# Rocket32_TRASIO_fixed.net
KiCad netlist of a schematic drawn in EAGLE
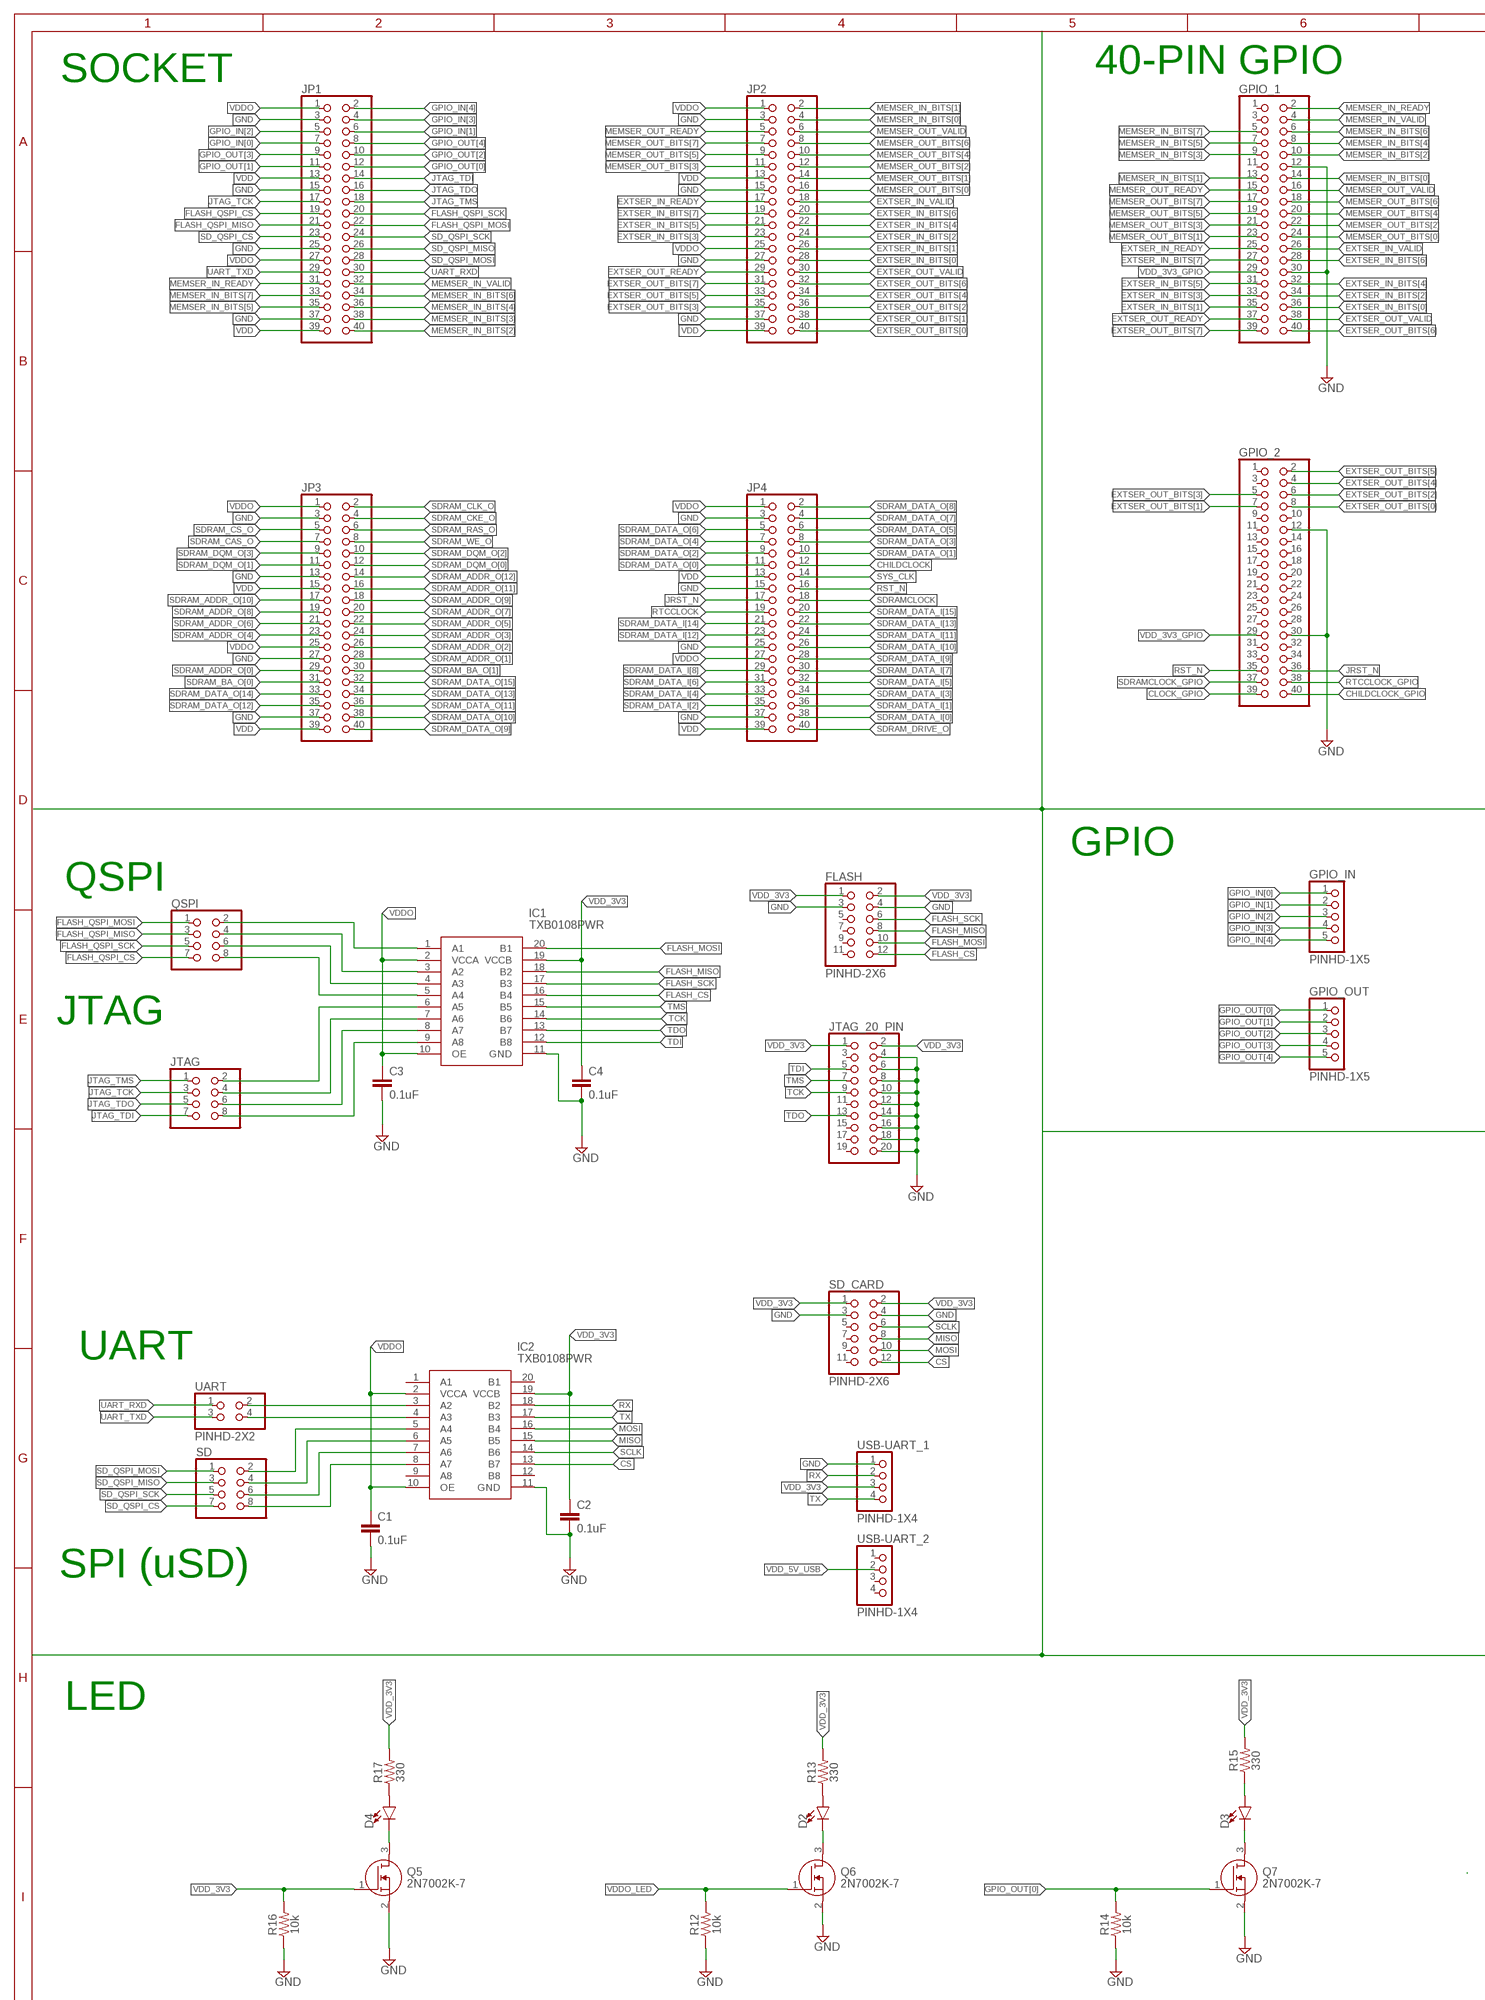
[diagram p0: schematic, sheet 1, part 1 of 2]
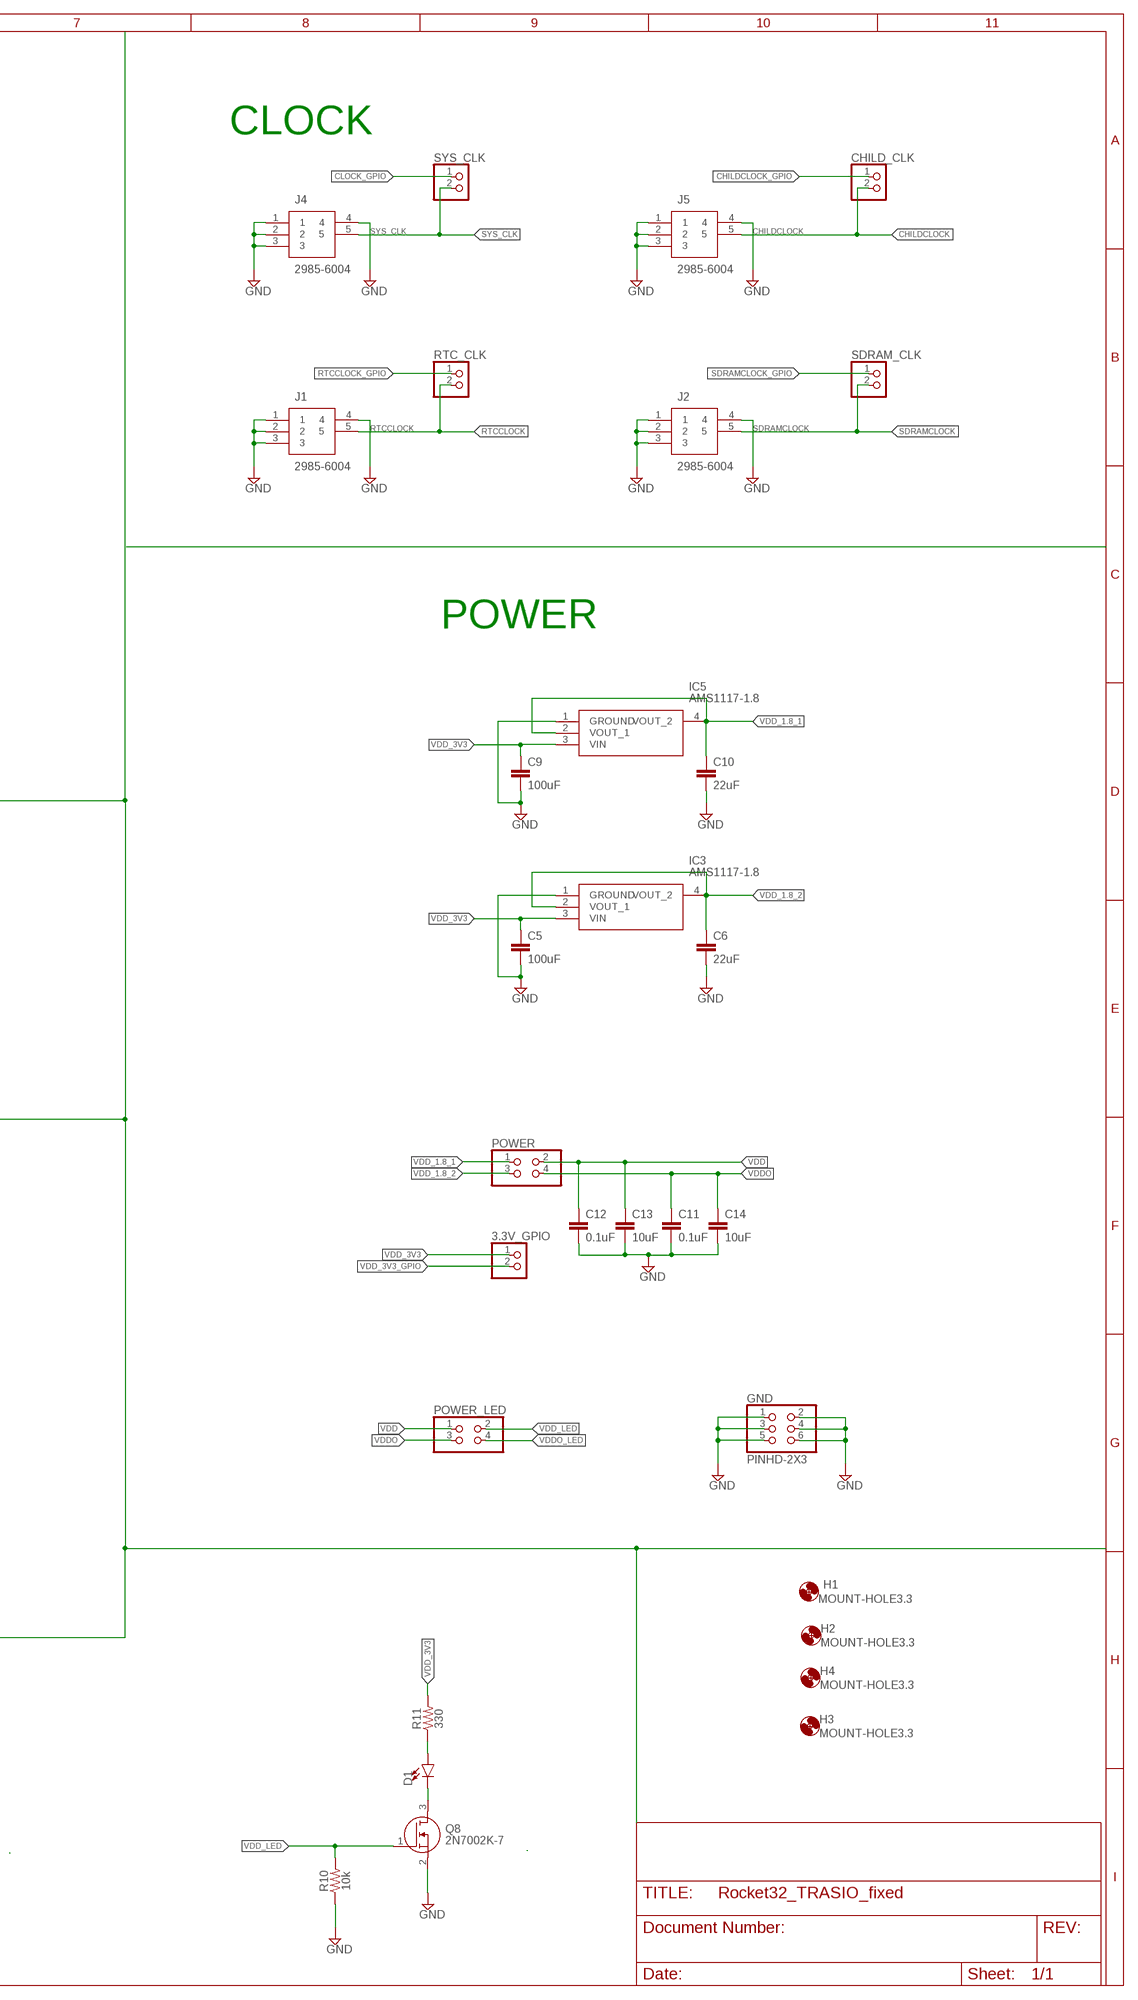
[diagram p1: schematic, sheet 1, part 2 of 2]

(export (version "E")
  (design (tool "Eeschema 10.0.6"))
  (components
    (comp (ref "3.3V_GPIO")
      (value "PINHD-1X2")
      (footprint "eagle-import:1X02")
      (libsource (lib "eagle-import") (part "PINHD-1X2"))
    )
    (comp (ref "C1")
      (value "0.1uF")
      (footprint "eagle-import:1206")
      (libsource (lib "eagle-import") (part "1.0UF-1206-50V-10%"))
    )
    (comp (ref "C2")
      (value "0.1uF")
      (footprint "eagle-import:1206")
      (libsource (lib "eagle-import") (part "1.0UF-1206-50V-10%"))
    )
    (comp (ref "C3")
      (value "0.1uF")
      (footprint "eagle-import:1206")
      (libsource (lib "eagle-import") (part "1.0UF-1206-50V-10%"))
    )
    (comp (ref "C4")
      (value "0.1uF")
      (footprint "eagle-import:1206")
      (libsource (lib "eagle-import") (part "1.0UF-1206-50V-10%"))
    )
    (comp (ref "C5")
      (value "100uF")
      (footprint "eagle-import:1206")
      (libsource (lib "eagle-import") (part "1.0UF-1206-50V-10%"))
    )
    (comp (ref "C6")
      (value "22uF")
      (footprint "eagle-import:1206")
      (libsource (lib "eagle-import") (part "1.0UF-1206-50V-10%"))
    )
    (comp (ref "C9")
      (value "100uF")
      (footprint "eagle-import:1206")
      (libsource (lib "eagle-import") (part "1.0UF-1206-50V-10%"))
    )
    (comp (ref "C10")
      (value "22uF")
      (footprint "eagle-import:1206")
      (libsource (lib "eagle-import") (part "1.0UF-1206-50V-10%"))
    )
    (comp (ref "C11")
      (value "0.1uF")
      (footprint "eagle-import:1206")
      (libsource (lib "eagle-import") (part "1.0UF-1206-50V-10%"))
    )
    (comp (ref "C12")
      (value "0.1uF")
      (footprint "eagle-import:1206")
      (libsource (lib "eagle-import") (part "1.0UF-1206-50V-10%"))
    )
    (comp (ref "C13")
      (value "10uF")
      (footprint "eagle-import:1206")
      (libsource (lib "eagle-import") (part "1.0UF-1206-50V-10%"))
    )
    (comp (ref "C14")
      (value "10uF")
      (footprint "eagle-import:1206")
      (libsource (lib "eagle-import") (part "1.0UF-1206-50V-10%"))
    )
    (comp (ref "CHILD_CLK")
      (value "PINHD-1X2")
      (footprint "eagle-import:1X02")
      (libsource (lib "eagle-import") (part "PINHD-1X2"))
    )
    (comp (ref "D1")
      (value "LED1206")
      (footprint "eagle-import:LED-1206")
      (libsource (lib "eagle-import") (part "LED1206"))
    )
    (comp (ref "D2")
      (value "LED1206")
      (footprint "eagle-import:LED-1206")
      (libsource (lib "eagle-import") (part "LED1206"))
    )
    (comp (ref "D3")
      (value "LED1206")
      (footprint "eagle-import:LED-1206")
      (libsource (lib "eagle-import") (part "LED1206"))
    )
    (comp (ref "D4")
      (value "LED1206")
      (footprint "eagle-import:LED-1206")
      (libsource (lib "eagle-import") (part "LED1206"))
    )
    (comp (ref "FLASH")
      (value "PINHD-2X6")
      (footprint "eagle-import:2X06")
      (libsource (lib "eagle-import") (part "PINHD-2X6"))
    )
    (comp (ref "GND")
      (value "PINHD-2X3")
      (footprint "eagle-import:2X03")
      (libsource (lib "eagle-import") (part "PINHD-2X3"))
    )
    (comp (ref "GPIO_1")
      (value "PINHD-2X20")
      (footprint "eagle-import:2X20")
      (libsource (lib "eagle-import") (part "PINHD-2X20"))
    )
    (comp (ref "GPIO_2")
      (value "PINHD-2X20")
      (footprint "eagle-import:2X20")
      (libsource (lib "eagle-import") (part "PINHD-2X20"))
    )
    (comp (ref "GPIO_IN")
      (value "PINHD-1X5")
      (footprint "eagle-import:1X05")
      (libsource (lib "eagle-import") (part "PINHD-1X5"))
    )
    (comp (ref "GPIO_OUT")
      (value "PINHD-1X5")
      (footprint "eagle-import:1X05")
      (libsource (lib "eagle-import") (part "PINHD-1X5"))
    )
    (comp (ref "H1")
      (value "MOUNT-HOLE3.3")
      (footprint "eagle-import:3,3")
      (libsource (lib "eagle-import") (part "MOUNT-HOLE3.3"))
    )
    (comp (ref "H2")
      (value "MOUNT-HOLE3.3")
      (footprint "eagle-import:3,3")
      (libsource (lib "eagle-import") (part "MOUNT-HOLE3.3"))
    )
    (comp (ref "H3")
      (value "MOUNT-HOLE3.3")
      (footprint "eagle-import:3,3")
      (libsource (lib "eagle-import") (part "MOUNT-HOLE3.3"))
    )
    (comp (ref "H4")
      (value "MOUNT-HOLE3.3")
      (footprint "eagle-import:3,3")
      (libsource (lib "eagle-import") (part "MOUNT-HOLE3.3"))
    )
    (comp (ref "IC1")
      (value "TXB0108PWR")
      (footprint "eagle-import:SOP65P640X120-20N")
      (fields (field (name "MOUSER_PART_NUMBER") "595-TXB0108PWR"))
      (libsource (lib "eagle-import") (part "TXB0108PWR"))
    )
    (comp (ref "IC2")
      (value "TXB0108PWR")
      (footprint "eagle-import:SOP65P640X120-20N")
      (fields (field (name "MOUSER_PART_NUMBER") "595-TXB0108PWR"))
      (libsource (lib "eagle-import") (part "TXB0108PWR"))
    )
    (comp (ref "IC3")
      (value "AMS1117-1.8")
      (footprint "eagle-import:SOT229P700X180-4N")
      (fields (field (name "MANUFACTURER_PART_NUMBER") "AMS1117"))
      (libsource (lib "eagle-import") (part "AMS1117"))
    )
    (comp (ref "IC5")
      (value "AMS1117-1.8")
      (footprint "eagle-import:SOT229P700X180-4N")
      (fields (field (name "MANUFACTURER_PART_NUMBER") "AMS1117"))
      (libsource (lib "eagle-import") (part "AMS1117"))
    )
    (comp (ref "J1")
      (value "2985-6004")
      (footprint "eagle-import:29856004")
      (fields (field (name "MOUSER_PART_NUMBER") "523-2985-6004"))
      (libsource (lib "eagle-import") (part "2985-6004"))
    )
    (comp (ref "J2")
      (value "2985-6004")
      (footprint "eagle-import:29856004")
      (fields (field (name "MOUSER_PART_NUMBER") "523-2985-6004"))
      (libsource (lib "eagle-import") (part "2985-6004"))
    )
    (comp (ref "J4")
      (value "2985-6004")
      (footprint "eagle-import:29856004")
      (fields (field (name "MOUSER_PART_NUMBER") "523-2985-6004"))
      (libsource (lib "eagle-import") (part "2985-6004"))
    )
    (comp (ref "J5")
      (value "2985-6004")
      (footprint "eagle-import:29856004")
      (fields (field (name "MOUSER_PART_NUMBER") "523-2985-6004"))
      (libsource (lib "eagle-import") (part "2985-6004"))
    )
    (comp (ref "JP1")
      (value "PINHD-2X20")
      (footprint "eagle-import:2X20")
      (libsource (lib "eagle-import") (part "PINHD-2X20"))
    )
    (comp (ref "JP2")
      (value "PINHD-2X20")
      (footprint "eagle-import:2X20")
      (libsource (lib "eagle-import") (part "PINHD-2X20"))
    )
    (comp (ref "JP3")
      (value "PINHD-2X20")
      (footprint "eagle-import:2X20")
      (libsource (lib "eagle-import") (part "PINHD-2X20"))
    )
    (comp (ref "JP4")
      (value "PINHD-2X20")
      (footprint "eagle-import:2X20")
      (libsource (lib "eagle-import") (part "PINHD-2X20"))
    )
    (comp (ref "JTAG")
      (value "PINHD-2X4")
      (footprint "eagle-import:2X04")
      (libsource (lib "eagle-import") (part "PINHD-2X4"))
    )
    (comp (ref "JTAG_20_PIN")
      (value "PINHD-2X10")
      (footprint "eagle-import:2X10")
      (libsource (lib "eagle-import") (part "PINHD-2X10"))
    )
    (comp (ref "POWER")
      (value "PINHD-2X2")
      (footprint "eagle-import:2X02")
      (libsource (lib "eagle-import") (part "pinhead_325_PINHD-2X2"))
    )
    (comp (ref "POWER_LED")
      (value "PINHD-2X2")
      (footprint "eagle-import:2X02")
      (libsource (lib "eagle-import") (part "pinhead_325_PINHD-2X2"))
    )
    (comp (ref "Q5")
      (value "2N7002K-7")
      (footprint "eagle-import:SOT96P240X100-3N")
      (fields (field (name "MOUSER_PART_NUMBER") "621-2N7002K-7"))
      (libsource (lib "eagle-import") (part "2N7002K-7"))
    )
    (comp (ref "Q6")
      (value "2N7002K-7")
      (footprint "eagle-import:SOT96P240X100-3N")
      (fields (field (name "MOUSER_PART_NUMBER") "621-2N7002K-7"))
      (libsource (lib "eagle-import") (part "2N7002K-7"))
    )
    (comp (ref "Q7")
      (value "2N7002K-7")
      (footprint "eagle-import:SOT96P240X100-3N")
      (fields (field (name "MOUSER_PART_NUMBER") "621-2N7002K-7"))
      (libsource (lib "eagle-import") (part "2N7002K-7"))
    )
    (comp (ref "Q8")
      (value "2N7002K-7")
      (footprint "eagle-import:SOT96P240X100-3N")
      (fields (field (name "MOUSER_PART_NUMBER") "621-2N7002K-7"))
      (libsource (lib "eagle-import") (part "2N7002K-7"))
    )
    (comp (ref "QSPI")
      (value "PINHD-2X4")
      (footprint "eagle-import:2X04")
      (libsource (lib "eagle-import") (part "PINHD-2X4"))
    )
    (comp (ref "R10")
      (value "10k")
      (footprint "eagle-import:1206")
      (libsource (lib "eagle-import") (part "RESISTOR1206"))
    )
    (comp (ref "R11")
      (value "330")
      (footprint "eagle-import:1206")
      (libsource (lib "eagle-import") (part "RESISTOR1206"))
    )
    (comp (ref "R12")
      (value "10k")
      (footprint "eagle-import:1206")
      (libsource (lib "eagle-import") (part "RESISTOR1206"))
    )
    (comp (ref "R13")
      (value "330")
      (footprint "eagle-import:1206")
      (libsource (lib "eagle-import") (part "RESISTOR1206"))
    )
    (comp (ref "R14")
      (value "10k")
      (footprint "eagle-import:1206")
      (libsource (lib "eagle-import") (part "RESISTOR1206"))
    )
    (comp (ref "R15")
      (value "330")
      (footprint "eagle-import:1206")
      (libsource (lib "eagle-import") (part "RESISTOR1206"))
    )
    (comp (ref "R16")
      (value "10k")
      (footprint "eagle-import:1206")
      (libsource (lib "eagle-import") (part "RESISTOR1206"))
    )
    (comp (ref "R17")
      (value "330")
      (footprint "eagle-import:1206")
      (libsource (lib "eagle-import") (part "RESISTOR1206"))
    )
    (comp (ref "RTC_CLK")
      (value "PINHD-1X2")
      (footprint "eagle-import:1X02")
      (libsource (lib "eagle-import") (part "PINHD-1X2"))
    )
    (comp (ref "SD")
      (value "PINHD-2X4")
      (footprint "eagle-import:2X04")
      (libsource (lib "eagle-import") (part "PINHD-2X4"))
    )
    (comp (ref "SDRAM_CLK")
      (value "PINHD-1X2")
      (footprint "eagle-import:1X02")
      (libsource (lib "eagle-import") (part "PINHD-1X2"))
    )
    (comp (ref "SD_CARD")
      (value "PINHD-2X6")
      (footprint "eagle-import:2X06")
      (libsource (lib "eagle-import") (part "PINHD-2X6"))
    )
    (comp (ref "SYS_CLK")
      (value "PINHD-1X2")
      (footprint "eagle-import:1X02")
      (libsource (lib "eagle-import") (part "PINHD-1X2"))
    )
    (comp (ref "UART")
      (value "PINHD-2X2")
      (footprint "eagle-import:2X02")
      (libsource (lib "eagle-import") (part "PINHD-2X2"))
    )
    (comp (ref "USB-UART_1")
      (value "PINHD-1X4")
      (footprint "eagle-import:1X04")
      (libsource (lib "eagle-import") (part "PINHD-1X4"))
    )
    (comp (ref "USB-UART_2")
      (value "PINHD-1X4")
      (footprint "eagle-import:1X04")
      (libsource (lib "eagle-import") (part "PINHD-1X4"))
    )
  )
  (nets
    (net (code "1") (name "CHILDCLOCK") (class "Default")
      (node (ref "CHILD_CLK") (pin "2") (pinfunction "2_2") (pintype "passive"))
      (node (ref "J5") (pin "5") (pinfunction "5_5") (pintype "bidirectional"))
      (node (ref "JP4") (pin "12") (pinfunction "12_12") (pintype "passive"))
    )
    (net (code "2") (name "CHILDCLOCK_GPIO") (class "Default")
      (node (ref "CHILD_CLK") (pin "1") (pinfunction "1_1") (pintype "passive"))
      (node (ref "GPIO_2") (pin "40") (pinfunction "40_40") (pintype "passive"))
    )
    (net (code "3") (name "CLOCK_GPIO") (class "Default")
      (node (ref "GPIO_2") (pin "39") (pinfunction "39_39") (pintype "passive"))
      (node (ref "SYS_CLK") (pin "1") (pinfunction "1_1") (pintype "passive"))
    )
    (net (code "4") (name "CS") (class "Default")
      (node (ref "IC2") (pin "13") (pinfunction "B7_13") (pintype "bidirectional"))
      (node (ref "SD_CARD") (pin "12") (pinfunction "12_12") (pintype "passive"))
    )
    (net (code "5") (name "EXTSER_IN_BITS[0]") (class "Default")
      (node (ref "GPIO_1") (pin "36") (pinfunction "36_36") (pintype "passive"))
      (node (ref "JP2") (pin "28") (pinfunction "28_28") (pintype "passive"))
    )
    (net (code "6") (name "EXTSER_IN_BITS[1]") (class "Default")
      (node (ref "GPIO_1") (pin "35") (pinfunction "35_35") (pintype "passive"))
      (node (ref "JP2") (pin "26") (pinfunction "26_26") (pintype "passive"))
    )
    (net (code "7") (name "EXTSER_IN_BITS[2]") (class "Default")
      (node (ref "GPIO_1") (pin "34") (pinfunction "34_34") (pintype "passive"))
      (node (ref "JP2") (pin "24") (pinfunction "24_24") (pintype "passive"))
    )
    (net (code "8") (name "EXTSER_IN_BITS[3]") (class "Default")
      (node (ref "GPIO_1") (pin "33") (pinfunction "33_33") (pintype "passive"))
      (node (ref "JP2") (pin "23") (pinfunction "23_23") (pintype "passive"))
    )
    (net (code "9") (name "EXTSER_IN_BITS[4]") (class "Default")
      (node (ref "GPIO_1") (pin "32") (pinfunction "32_32") (pintype "passive"))
      (node (ref "JP2") (pin "22") (pinfunction "22_22") (pintype "passive"))
    )
    (net (code "10") (name "EXTSER_IN_BITS[5]") (class "Default")
      (node (ref "GPIO_1") (pin "31") (pinfunction "31_31") (pintype "passive"))
      (node (ref "JP2") (pin "21") (pinfunction "21_21") (pintype "passive"))
    )
    (net (code "11") (name "EXTSER_IN_BITS[6]") (class "Default")
      (node (ref "GPIO_1") (pin "28") (pinfunction "28_28") (pintype "passive"))
      (node (ref "JP2") (pin "20") (pinfunction "20_20") (pintype "passive"))
    )
    (net (code "12") (name "EXTSER_IN_BITS[7]") (class "Default")
      (node (ref "GPIO_1") (pin "27") (pinfunction "27_27") (pintype "passive"))
      (node (ref "JP2") (pin "19") (pinfunction "19_19") (pintype "passive"))
    )
    (net (code "13") (name "EXTSER_IN_READY") (class "Default")
      (node (ref "GPIO_1") (pin "25") (pinfunction "25_25") (pintype "passive"))
      (node (ref "JP2") (pin "17") (pinfunction "17_17") (pintype "passive"))
    )
    (net (code "14") (name "EXTSER_IN_VALID") (class "Default")
      (node (ref "GPIO_1") (pin "26") (pinfunction "26_26") (pintype "passive"))
      (node (ref "JP2") (pin "18") (pinfunction "18_18") (pintype "passive"))
    )
    (net (code "15") (name "EXTSER_OUT_BITS[0]") (class "Default")
      (node (ref "GPIO_2") (pin "8") (pinfunction "8_8") (pintype "passive"))
      (node (ref "JP2") (pin "40") (pinfunction "40_40") (pintype "passive"))
    )
    (net (code "16") (name "EXTSER_OUT_BITS[1]") (class "Default")
      (node (ref "GPIO_2") (pin "7") (pinfunction "7_7") (pintype "passive"))
      (node (ref "JP2") (pin "38") (pinfunction "38_38") (pintype "passive"))
    )
    (net (code "17") (name "EXTSER_OUT_BITS[2]") (class "Default")
      (node (ref "GPIO_2") (pin "6") (pinfunction "6_6") (pintype "passive"))
      (node (ref "JP2") (pin "36") (pinfunction "36_36") (pintype "passive"))
    )
    (net (code "18") (name "EXTSER_OUT_BITS[3]") (class "Default")
      (node (ref "GPIO_2") (pin "5") (pinfunction "5_5") (pintype "passive"))
      (node (ref "JP2") (pin "35") (pinfunction "35_35") (pintype "passive"))
    )
    (net (code "19") (name "EXTSER_OUT_BITS[4]") (class "Default")
      (node (ref "GPIO_2") (pin "4") (pinfunction "4_4") (pintype "passive"))
      (node (ref "JP2") (pin "34") (pinfunction "34_34") (pintype "passive"))
    )
    (net (code "20") (name "EXTSER_OUT_BITS[5]") (class "Default")
      (node (ref "GPIO_2") (pin "2") (pinfunction "2_2") (pintype "passive"))
      (node (ref "JP2") (pin "33") (pinfunction "33_33") (pintype "passive"))
    )
    (net (code "21") (name "EXTSER_OUT_BITS[6]") (class "Default")
      (node (ref "GPIO_1") (pin "40") (pinfunction "40_40") (pintype "passive"))
      (node (ref "JP2") (pin "32") (pinfunction "32_32") (pintype "passive"))
    )
    (net (code "22") (name "EXTSER_OUT_BITS[7]") (class "Default")
      (node (ref "GPIO_1") (pin "39") (pinfunction "39_39") (pintype "passive"))
      (node (ref "JP2") (pin "31") (pinfunction "31_31") (pintype "passive"))
    )
    (net (code "23") (name "EXTSER_OUT_READY") (class "Default")
      (node (ref "GPIO_1") (pin "37") (pinfunction "37_37") (pintype "passive"))
      (node (ref "JP2") (pin "29") (pinfunction "29_29") (pintype "passive"))
    )
    (net (code "24") (name "EXTSER_OUT_VALID") (class "Default")
      (node (ref "GPIO_1") (pin "38") (pinfunction "38_38") (pintype "passive"))
      (node (ref "JP2") (pin "30") (pinfunction "30_30") (pintype "passive"))
    )
    (net (code "25") (name "FLASH_CS") (class "Default")
      (node (ref "FLASH") (pin "12") (pinfunction "12_12") (pintype "passive"))
      (node (ref "IC1") (pin "16") (pinfunction "B4_16") (pintype "bidirectional"))
    )
    (net (code "26") (name "FLASH_MISO") (class "Default")
      (node (ref "FLASH") (pin "8") (pinfunction "8_8") (pintype "passive"))
      (node (ref "IC1") (pin "18") (pinfunction "B2_18") (pintype "bidirectional"))
    )
    (net (code "27") (name "FLASH_MOSI") (class "Default")
      (node (ref "FLASH") (pin "10") (pinfunction "10_10") (pintype "passive"))
      (node (ref "IC1") (pin "20") (pinfunction "B1_20") (pintype "bidirectional"))
    )
    (net (code "28") (name "FLASH_QSPI_CS") (class "Default")
      (node (ref "JP1") (pin "19") (pinfunction "19_19") (pintype "passive"))
      (node (ref "QSPI") (pin "7") (pinfunction "7_7") (pintype "passive"))
    )
    (net (code "29") (name "FLASH_QSPI_MISO") (class "Default")
      (node (ref "JP1") (pin "21") (pinfunction "21_21") (pintype "passive"))
      (node (ref "QSPI") (pin "3") (pinfunction "3_3") (pintype "passive"))
    )
    (net (code "30") (name "FLASH_QSPI_MOSI") (class "Default")
      (node (ref "JP1") (pin "22") (pinfunction "22_22") (pintype "passive"))
      (node (ref "QSPI") (pin "1") (pinfunction "1_1") (pintype "passive"))
    )
    (net (code "31") (name "FLASH_QSPI_SCK") (class "Default")
      (node (ref "JP1") (pin "20") (pinfunction "20_20") (pintype "passive"))
      (node (ref "QSPI") (pin "5") (pinfunction "5_5") (pintype "passive"))
    )
    (net (code "32") (name "FLASH_SCK") (class "Default")
      (node (ref "FLASH") (pin "6") (pinfunction "6_6") (pintype "passive"))
      (node (ref "IC1") (pin "17") (pinfunction "B3_17") (pintype "bidirectional"))
    )
    (net (code "33") (name "GND") (class "Default")
      (node (ref "C1") (pin "2") (pinfunction "2_2") (pintype "passive"))
      (node (ref "C10") (pin "2") (pinfunction "2_2") (pintype "passive"))
      (node (ref "C11") (pin "2") (pinfunction "2_2") (pintype "passive"))
      (node (ref "C12") (pin "2") (pinfunction "2_2") (pintype "passive"))
      (node (ref "C13") (pin "2") (pinfunction "2_2") (pintype "passive"))
      (node (ref "C14") (pin "2") (pinfunction "2_2") (pintype "passive"))
      (node (ref "C2") (pin "2") (pinfunction "2_2") (pintype "passive"))
      (node (ref "C3") (pin "2") (pinfunction "2_2") (pintype "passive"))
      (node (ref "C4") (pin "2") (pinfunction "2_2") (pintype "passive"))
      (node (ref "C5") (pin "2") (pinfunction "2_2") (pintype "passive"))
      (node (ref "C6") (pin "2") (pinfunction "2_2") (pintype "passive"))
      (node (ref "C9") (pin "2") (pinfunction "2_2") (pintype "passive"))
      (node (ref "FLASH") (pin "3") (pinfunction "3_3") (pintype "passive"))
      (node (ref "FLASH") (pin "4") (pinfunction "4_4") (pintype "passive"))
      (node (ref "GND") (pin "1") (pinfunction "1_1") (pintype "passive"))
      (node (ref "GND") (pin "2") (pinfunction "2_2") (pintype "passive"))
      (node (ref "GND") (pin "3") (pinfunction "3_3") (pintype "passive"))
      (node (ref "GND") (pin "4") (pinfunction "4_4") (pintype "passive"))
      (node (ref "GND") (pin "5") (pinfunction "5_5") (pintype "passive"))
      (node (ref "GND") (pin "6") (pinfunction "6_6") (pintype "passive"))
      (node (ref "GPIO_1") (pin "12") (pinfunction "12_12") (pintype "passive"))
      (node (ref "GPIO_1") (pin "30") (pinfunction "30_30") (pintype "passive"))
      (node (ref "GPIO_2") (pin "12") (pinfunction "12_12") (pintype "passive"))
      (node (ref "GPIO_2") (pin "30") (pinfunction "30_30") (pintype "passive"))
      (node (ref "IC1") (pin "11") (pinfunction "GND_11") (pintype "bidirectional"))
      (node (ref "IC2") (pin "11") (pinfunction "GND_11") (pintype "bidirectional"))
      (node (ref "IC3") (pin "1") (pinfunction "GROUND_1") (pintype "bidirectional"))
      (node (ref "IC5") (pin "1") (pinfunction "GROUND_1") (pintype "bidirectional"))
      (node (ref "J1") (pin "1") (pinfunction "1_1") (pintype "bidirectional"))
      (node (ref "J1") (pin "2") (pinfunction "2_2") (pintype "bidirectional"))
      (node (ref "J1") (pin "3") (pinfunction "3_3") (pintype "bidirectional"))
      (node (ref "J1") (pin "4") (pinfunction "4_4") (pintype "bidirectional"))
      (node (ref "J2") (pin "1") (pinfunction "1_1") (pintype "bidirectional"))
      (node (ref "J2") (pin "2") (pinfunction "2_2") (pintype "bidirectional"))
      (node (ref "J2") (pin "3") (pinfunction "3_3") (pintype "bidirectional"))
      (node (ref "J2") (pin "4") (pinfunction "4_4") (pintype "bidirectional"))
      (node (ref "J4") (pin "1") (pinfunction "1_1") (pintype "bidirectional"))
      (node (ref "J4") (pin "2") (pinfunction "2_2") (pintype "bidirectional"))
      (node (ref "J4") (pin "3") (pinfunction "3_3") (pintype "bidirectional"))
      (node (ref "J4") (pin "4") (pinfunction "4_4") (pintype "bidirectional"))
      (node (ref "J5") (pin "1") (pinfunction "1_1") (pintype "bidirectional"))
      (node (ref "J5") (pin "2") (pinfunction "2_2") (pintype "bidirectional"))
      (node (ref "J5") (pin "3") (pinfunction "3_3") (pintype "bidirectional"))
      (node (ref "J5") (pin "4") (pinfunction "4_4") (pintype "bidirectional"))
      (node (ref "JP1") (pin "15") (pinfunction "15_15") (pintype "passive"))
      (node (ref "JP1") (pin "25") (pinfunction "25_25") (pintype "passive"))
      (node (ref "JP1") (pin "3") (pinfunction "3_3") (pintype "passive"))
      (node (ref "JP1") (pin "37") (pinfunction "37_37") (pintype "passive"))
      (node (ref "JP2") (pin "15") (pinfunction "15_15") (pintype "passive"))
      (node (ref "JP2") (pin "27") (pinfunction "27_27") (pintype "passive"))
      (node (ref "JP2") (pin "3") (pinfunction "3_3") (pintype "passive"))
      (node (ref "JP2") (pin "37") (pinfunction "37_37") (pintype "passive"))
      (node (ref "JP3") (pin "13") (pinfunction "13_13") (pintype "passive"))
      (node (ref "JP3") (pin "27") (pinfunction "27_27") (pintype "passive"))
      (node (ref "JP3") (pin "3") (pinfunction "3_3") (pintype "passive"))
      (node (ref "JP3") (pin "37") (pinfunction "37_37") (pintype "passive"))
      (node (ref "JP4") (pin "15") (pinfunction "15_15") (pintype "passive"))
      (node (ref "JP4") (pin "25") (pinfunction "25_25") (pintype "passive"))
      (node (ref "JP4") (pin "3") (pinfunction "3_3") (pintype "passive"))
      (node (ref "JP4") (pin "37") (pinfunction "37_37") (pintype "passive"))
      (node (ref "JTAG_20_PIN") (pin "10") (pinfunction "10_10") (pintype "passive"))
      (node (ref "JTAG_20_PIN") (pin "12") (pinfunction "12_12") (pintype "passive"))
      (node (ref "JTAG_20_PIN") (pin "14") (pinfunction "14_14") (pintype "passive"))
      (node (ref "JTAG_20_PIN") (pin "16") (pinfunction "16_16") (pintype "passive"))
      (node (ref "JTAG_20_PIN") (pin "18") (pinfunction "18_18") (pintype "passive"))
      (node (ref "JTAG_20_PIN") (pin "20") (pinfunction "20_20") (pintype "passive"))
      (node (ref "JTAG_20_PIN") (pin "4") (pinfunction "4_4") (pintype "passive"))
      (node (ref "JTAG_20_PIN") (pin "6") (pinfunction "6_6") (pintype "passive"))
      (node (ref "JTAG_20_PIN") (pin "8") (pinfunction "8_8") (pintype "passive"))
      (node (ref "Q5") (pin "2") (pinfunction "S_2") (pintype "bidirectional"))
      (node (ref "Q6") (pin "2") (pinfunction "S_2") (pintype "bidirectional"))
      (node (ref "Q7") (pin "2") (pinfunction "S_2") (pintype "bidirectional"))
      (node (ref "Q8") (pin "2") (pinfunction "S_2") (pintype "bidirectional"))
      (node (ref "R10") (pin "1") (pinfunction "1_1") (pintype "passive"))
      (node (ref "R12") (pin "1") (pinfunction "1_1") (pintype "passive"))
      (node (ref "R14") (pin "1") (pinfunction "1_1") (pintype "passive"))
      (node (ref "R16") (pin "1") (pinfunction "1_1") (pintype "passive"))
      (node (ref "SD_CARD") (pin "3") (pinfunction "3_3") (pintype "passive"))
      (node (ref "SD_CARD") (pin "4") (pinfunction "4_4") (pintype "passive"))
      (node (ref "USB-UART_1") (pin "1") (pinfunction "1_1") (pintype "passive"))
    )
    (net (code "34") (name "GPIO_IN[0]") (class "Default")
      (node (ref "GPIO_IN") (pin "1") (pinfunction "1_1") (pintype "passive"))
      (node (ref "JP1") (pin "7") (pinfunction "7_7") (pintype "passive"))
    )
    (net (code "35") (name "GPIO_IN[1]") (class "Default")
      (node (ref "GPIO_IN") (pin "2") (pinfunction "2_2") (pintype "passive"))
      (node (ref "JP1") (pin "6") (pinfunction "6_6") (pintype "passive"))
    )
    (net (code "36") (name "GPIO_IN[2]") (class "Default")
      (node (ref "GPIO_IN") (pin "3") (pinfunction "3_3") (pintype "passive"))
      (node (ref "JP1") (pin "5") (pinfunction "5_5") (pintype "passive"))
    )
    (net (code "37") (name "GPIO_IN[3]") (class "Default")
      (node (ref "GPIO_IN") (pin "4") (pinfunction "4_4") (pintype "passive"))
      (node (ref "JP1") (pin "4") (pinfunction "4_4") (pintype "passive"))
    )
    (net (code "38") (name "GPIO_IN[4]") (class "Default")
      (node (ref "GPIO_IN") (pin "5") (pinfunction "5_5") (pintype "passive"))
      (node (ref "JP1") (pin "2") (pinfunction "2_2") (pintype "passive"))
    )
    (net (code "39") (name "GPIO_OUT[0]") (class "Default")
      (node (ref "GPIO_OUT") (pin "1") (pinfunction "1_1") (pintype "passive"))
      (node (ref "JP1") (pin "12") (pinfunction "12_12") (pintype "passive"))
      (node (ref "Q7") (pin "1") (pinfunction "G_1") (pintype "bidirectional"))
      (node (ref "R14") (pin "2") (pinfunction "2_2") (pintype "passive"))
    )
    (net (code "40") (name "GPIO_OUT[1]") (class "Default")
      (node (ref "GPIO_OUT") (pin "2") (pinfunction "2_2") (pintype "passive"))
      (node (ref "JP1") (pin "11") (pinfunction "11_11") (pintype "passive"))
    )
    (net (code "41") (name "GPIO_OUT[2]") (class "Default")
      (node (ref "GPIO_OUT") (pin "3") (pinfunction "3_3") (pintype "passive"))
      (node (ref "JP1") (pin "10") (pinfunction "10_10") (pintype "passive"))
    )
    (net (code "42") (name "GPIO_OUT[3]") (class "Default")
      (node (ref "GPIO_OUT") (pin "4") (pinfunction "4_4") (pintype "passive"))
      (node (ref "JP1") (pin "9") (pinfunction "9_9") (pintype "passive"))
    )
    (net (code "43") (name "GPIO_OUT[4]") (class "Default")
      (node (ref "GPIO_OUT") (pin "5") (pinfunction "5_5") (pintype "passive"))
      (node (ref "JP1") (pin "8") (pinfunction "8_8") (pintype "passive"))
    )
    (net (code "44") (name "JRST_N") (class "Default")
      (node (ref "GPIO_2") (pin "36") (pinfunction "36_36") (pintype "passive"))
      (node (ref "JP4") (pin "17") (pinfunction "17_17") (pintype "passive"))
    )
    (net (code "45") (name "JTAG_TCK") (class "Default")
      (node (ref "JP1") (pin "17") (pinfunction "17_17") (pintype "passive"))
      (node (ref "JTAG") (pin "3") (pinfunction "3_3") (pintype "passive"))
    )
    (net (code "46") (name "JTAG_TDI") (class "Default")
      (node (ref "JP1") (pin "14") (pinfunction "14_14") (pintype "passive"))
      (node (ref "JTAG") (pin "7") (pinfunction "7_7") (pintype "passive"))
    )
    (net (code "47") (name "JTAG_TDO") (class "Default")
      (node (ref "JP1") (pin "16") (pinfunction "16_16") (pintype "passive"))
      (node (ref "JTAG") (pin "5") (pinfunction "5_5") (pintype "passive"))
    )
    (net (code "48") (name "JTAG_TMS") (class "Default")
      (node (ref "JP1") (pin "18") (pinfunction "18_18") (pintype "passive"))
      (node (ref "JTAG") (pin "1") (pinfunction "1_1") (pintype "passive"))
    )
    (net (code "49") (name "MEMSER_IN_BITS[0]") (class "Default")
      (node (ref "GPIO_1") (pin "14") (pinfunction "14_14") (pintype "passive"))
      (node (ref "JP2") (pin "4") (pinfunction "4_4") (pintype "passive"))
    )
    (net (code "50") (name "MEMSER_IN_BITS[1]") (class "Default")
      (node (ref "GPIO_1") (pin "13") (pinfunction "13_13") (pintype "passive"))
      (node (ref "JP2") (pin "2") (pinfunction "2_2") (pintype "passive"))
    )
    (net (code "51") (name "MEMSER_IN_BITS[2]") (class "Default")
      (node (ref "GPIO_1") (pin "10") (pinfunction "10_10") (pintype "passive"))
      (node (ref "JP1") (pin "40") (pinfunction "40_40") (pintype "passive"))
    )
    (net (code "52") (name "MEMSER_IN_BITS[3]") (class "Default")
      (node (ref "GPIO_1") (pin "9") (pinfunction "9_9") (pintype "passive"))
      (node (ref "JP1") (pin "38") (pinfunction "38_38") (pintype "passive"))
    )
    (net (code "53") (name "MEMSER_IN_BITS[4]") (class "Default")
      (node (ref "GPIO_1") (pin "8") (pinfunction "8_8") (pintype "passive"))
      (node (ref "JP1") (pin "36") (pinfunction "36_36") (pintype "passive"))
    )
    (net (code "54") (name "MEMSER_IN_BITS[5]") (class "Default")
      (node (ref "GPIO_1") (pin "7") (pinfunction "7_7") (pintype "passive"))
      (node (ref "JP1") (pin "35") (pinfunction "35_35") (pintype "passive"))
    )
    (net (code "55") (name "MEMSER_IN_BITS[6]") (class "Default")
      (node (ref "GPIO_1") (pin "6") (pinfunction "6_6") (pintype "passive"))
      (node (ref "JP1") (pin "34") (pinfunction "34_34") (pintype "passive"))
    )
    (net (code "56") (name "MEMSER_IN_BITS[7]") (class "Default")
      (node (ref "GPIO_1") (pin "5") (pinfunction "5_5") (pintype "passive"))
      (node (ref "JP1") (pin "33") (pinfunction "33_33") (pintype "passive"))
    )
    (net (code "57") (name "MEMSER_IN_READY") (class "Default")
      (node (ref "GPIO_1") (pin "2") (pinfunction "2_2") (pintype "passive"))
      (node (ref "JP1") (pin "31") (pinfunction "31_31") (pintype "passive"))
    )
    (net (code "58") (name "MEMSER_IN_VALID") (class "Default")
      (node (ref "GPIO_1") (pin "4") (pinfunction "4_4") (pintype "passive"))
      (node (ref "JP1") (pin "32") (pinfunction "32_32") (pintype "passive"))
    )
    (net (code "59") (name "MEMSER_OUT_BITS[0]") (class "Default")
      (node (ref "GPIO_1") (pin "24") (pinfunction "24_24") (pintype "passive"))
      (node (ref "JP2") (pin "16") (pinfunction "16_16") (pintype "passive"))
    )
    (net (code "60") (name "MEMSER_OUT_BITS[1]") (class "Default")
      (node (ref "GPIO_1") (pin "23") (pinfunction "23_23") (pintype "passive"))
      (node (ref "JP2") (pin "14") (pinfunction "14_14") (pintype "passive"))
    )
    (net (code "61") (name "MEMSER_OUT_BITS[2]") (class "Default")
      (node (ref "GPIO_1") (pin "22") (pinfunction "22_22") (pintype "passive"))
      (node (ref "JP2") (pin "12") (pinfunction "12_12") (pintype "passive"))
    )
    (net (code "62") (name "MEMSER_OUT_BITS[3]") (class "Default")
      (node (ref "GPIO_1") (pin "21") (pinfunction "21_21") (pintype "passive"))
      (node (ref "JP2") (pin "11") (pinfunction "11_11") (pintype "passive"))
    )
    (net (code "63") (name "MEMSER_OUT_BITS[4]") (class "Default")
      (node (ref "GPIO_1") (pin "20") (pinfunction "20_20") (pintype "passive"))
      (node (ref "JP2") (pin "10") (pinfunction "10_10") (pintype "passive"))
    )
    (net (code "64") (name "MEMSER_OUT_BITS[5]") (class "Default")
      (node (ref "GPIO_1") (pin "19") (pinfunction "19_19") (pintype "passive"))
      (node (ref "JP2") (pin "9") (pinfunction "9_9") (pintype "passive"))
    )
    (net (code "65") (name "MEMSER_OUT_BITS[6]") (class "Default")
      (node (ref "GPIO_1") (pin "18") (pinfunction "18_18") (pintype "passive"))
      (node (ref "JP2") (pin "8") (pinfunction "8_8") (pintype "passive"))
    )
    (net (code "66") (name "MEMSER_OUT_BITS[7]") (class "Default")
      (node (ref "GPIO_1") (pin "17") (pinfunction "17_17") (pintype "passive"))
      (node (ref "JP2") (pin "7") (pinfunction "7_7") (pintype "passive"))
    )
    (net (code "67") (name "MEMSER_OUT_READY") (class "Default")
      (node (ref "GPIO_1") (pin "15") (pinfunction "15_15") (pintype "passive"))
      (node (ref "JP2") (pin "5") (pinfunction "5_5") (pintype "passive"))
    )
    (net (code "68") (name "MEMSER_OUT_VALID") (class "Default")
      (node (ref "GPIO_1") (pin "16") (pinfunction "16_16") (pintype "passive"))
      (node (ref "JP2") (pin "6") (pinfunction "6_6") (pintype "passive"))
    )
    (net (code "69") (name "MISO") (class "Default")
      (node (ref "IC2") (pin "15") (pinfunction "B5_15") (pintype "bidirectional"))
      (node (ref "SD_CARD") (pin "8") (pinfunction "8_8") (pintype "passive"))
    )
    (net (code "70") (name "MOSI") (class "Default")
      (node (ref "IC2") (pin "16") (pinfunction "B4_16") (pintype "bidirectional"))
      (node (ref "SD_CARD") (pin "10") (pinfunction "10_10") (pintype "passive"))
    )
    (net (code "71") (name "Net-(D1-PadA)") (class "Default")
      (node (ref "D1") (pin "A") (pinfunction "A_A") (pintype "passive"))
      (node (ref "R11") (pin "1") (pinfunction "1_1") (pintype "passive"))
    )
    (net (code "72") (name "Net-(D2-PadA)") (class "Default")
      (node (ref "D2") (pin "A") (pinfunction "A_A") (pintype "passive"))
      (node (ref "R13") (pin "1") (pinfunction "1_1") (pintype "passive"))
    )
    (net (code "73") (name "Net-(D3-PadA)") (class "Default")
      (node (ref "D3") (pin "A") (pinfunction "A_A") (pintype "passive"))
      (node (ref "R15") (pin "1") (pinfunction "1_1") (pintype "passive"))
    )
    (net (code "74") (name "Net-(D4-PadA)") (class "Default")
      (node (ref "D4") (pin "A") (pinfunction "A_A") (pintype "passive"))
      (node (ref "R17") (pin "1") (pinfunction "1_1") (pintype "passive"))
    )
    (net (code "75") (name "Net-(IC1-A1)") (class "Default")
      (node (ref "IC1") (pin "1") (pinfunction "A1_1") (pintype "bidirectional"))
      (node (ref "QSPI") (pin "2") (pinfunction "2_2") (pintype "passive"))
    )
    (net (code "76") (name "Net-(IC1-A2)") (class "Default")
      (node (ref "IC1") (pin "3") (pinfunction "A2_3") (pintype "bidirectional"))
      (node (ref "QSPI") (pin "4") (pinfunction "4_4") (pintype "passive"))
    )
    (net (code "77") (name "Net-(IC1-A3)") (class "Default")
      (node (ref "IC1") (pin "4") (pinfunction "A3_4") (pintype "bidirectional"))
      (node (ref "QSPI") (pin "6") (pinfunction "6_6") (pintype "passive"))
    )
    (net (code "78") (name "Net-(IC1-A4)") (class "Default")
      (node (ref "IC1") (pin "5") (pinfunction "A4_5") (pintype "bidirectional"))
      (node (ref "QSPI") (pin "8") (pinfunction "8_8") (pintype "passive"))
    )
    (net (code "79") (name "Net-(IC1-A5)") (class "Default")
      (node (ref "IC1") (pin "6") (pinfunction "A5_6") (pintype "bidirectional"))
      (node (ref "JTAG") (pin "2") (pinfunction "2_2") (pintype "passive"))
    )
    (net (code "80") (name "Net-(IC1-A6)") (class "Default")
      (node (ref "IC1") (pin "7") (pinfunction "A6_7") (pintype "bidirectional"))
      (node (ref "JTAG") (pin "4") (pinfunction "4_4") (pintype "passive"))
    )
    (net (code "81") (name "Net-(IC1-A7)") (class "Default")
      (node (ref "IC1") (pin "8") (pinfunction "A7_8") (pintype "bidirectional"))
      (node (ref "JTAG") (pin "6") (pinfunction "6_6") (pintype "passive"))
    )
    (net (code "82") (name "Net-(IC1-A8)") (class "Default")
      (node (ref "IC1") (pin "9") (pinfunction "A8_9") (pintype "bidirectional"))
      (node (ref "JTAG") (pin "8") (pinfunction "8_8") (pintype "passive"))
    )
    (net (code "83") (name "Net-(IC2-A2)") (class "Default")
      (node (ref "IC2") (pin "3") (pinfunction "A2_3") (pintype "bidirectional"))
      (node (ref "UART") (pin "2") (pinfunction "2_2") (pintype "passive"))
    )
    (net (code "84") (name "Net-(IC2-A3)") (class "Default")
      (node (ref "IC2") (pin "4") (pinfunction "A3_4") (pintype "bidirectional"))
      (node (ref "UART") (pin "4") (pinfunction "4_4") (pintype "passive"))
    )
    (net (code "85") (name "Net-(IC2-A4)") (class "Default")
      (node (ref "IC2") (pin "5") (pinfunction "A4_5") (pintype "bidirectional"))
      (node (ref "SD") (pin "2") (pinfunction "2_2") (pintype "passive"))
    )
    (net (code "86") (name "Net-(IC2-A5)") (class "Default")
      (node (ref "IC2") (pin "6") (pinfunction "A5_6") (pintype "bidirectional"))
      (node (ref "SD") (pin "4") (pinfunction "4_4") (pintype "passive"))
    )
    (net (code "87") (name "Net-(IC2-A6)") (class "Default")
      (node (ref "IC2") (pin "7") (pinfunction "A6_7") (pintype "bidirectional"))
      (node (ref "SD") (pin "6") (pinfunction "6_6") (pintype "passive"))
    )
    (net (code "88") (name "Net-(IC2-A7)") (class "Default")
      (node (ref "IC2") (pin "8") (pinfunction "A7_8") (pintype "bidirectional"))
      (node (ref "SD") (pin "8") (pinfunction "8_8") (pintype "passive"))
    )
    (net (code "89") (name "Net-(Q5-D)") (class "Default")
      (node (ref "D4") (pin "C") (pinfunction "C_C") (pintype "passive"))
      (node (ref "Q5") (pin "3") (pinfunction "D_3") (pintype "bidirectional"))
    )
    (net (code "90") (name "Net-(Q6-D)") (class "Default")
      (node (ref "D2") (pin "C") (pinfunction "C_C") (pintype "passive"))
      (node (ref "Q6") (pin "3") (pinfunction "D_3") (pintype "bidirectional"))
    )
    (net (code "91") (name "Net-(Q7-D)") (class "Default")
      (node (ref "D3") (pin "C") (pinfunction "C_C") (pintype "passive"))
      (node (ref "Q7") (pin "3") (pinfunction "D_3") (pintype "bidirectional"))
    )
    (net (code "92") (name "Net-(Q8-D)") (class "Default")
      (node (ref "D1") (pin "C") (pinfunction "C_C") (pintype "passive"))
      (node (ref "Q8") (pin "3") (pinfunction "D_3") (pintype "bidirectional"))
    )
    (net (code "93") (name "RST_N") (class "Default")
      (node (ref "GPIO_2") (pin "35") (pinfunction "35_35") (pintype "passive"))
      (node (ref "JP4") (pin "16") (pinfunction "16_16") (pintype "passive"))
    )
    (net (code "94") (name "RTCCLOCK") (class "Default")
      (node (ref "J1") (pin "5") (pinfunction "5_5") (pintype "bidirectional"))
      (node (ref "JP4") (pin "19") (pinfunction "19_19") (pintype "passive"))
      (node (ref "RTC_CLK") (pin "2") (pinfunction "2_2") (pintype "passive"))
    )
    (net (code "95") (name "RTCCLOCK_GPIO") (class "Default")
      (node (ref "GPIO_2") (pin "38") (pinfunction "38_38") (pintype "passive"))
      (node (ref "RTC_CLK") (pin "1") (pinfunction "1_1") (pintype "passive"))
    )
    (net (code "96") (name "RX") (class "Default")
      (node (ref "IC2") (pin "18") (pinfunction "B2_18") (pintype "bidirectional"))
      (node (ref "USB-UART_1") (pin "2") (pinfunction "2_2") (pintype "passive"))
    )
    (net (code "97") (name "SCLK") (class "Default")
      (node (ref "IC2") (pin "14") (pinfunction "B6_14") (pintype "bidirectional"))
      (node (ref "SD_CARD") (pin "6") (pinfunction "6_6") (pintype "passive"))
    )
    (net (code "98") (name "SDRAMCLOCK") (class "Default")
      (node (ref "J2") (pin "5") (pinfunction "5_5") (pintype "bidirectional"))
      (node (ref "JP4") (pin "18") (pinfunction "18_18") (pintype "passive"))
      (node (ref "SDRAM_CLK") (pin "2") (pinfunction "2_2") (pintype "passive"))
    )
    (net (code "99") (name "SDRAMCLOCK_GPIO") (class "Default")
      (node (ref "GPIO_2") (pin "37") (pinfunction "37_37") (pintype "passive"))
      (node (ref "SDRAM_CLK") (pin "1") (pinfunction "1_1") (pintype "passive"))
    )
    (net (code "100") (name "SDRAM_ADDR_O[0]") (class "Default")
      (node (ref "JP3") (pin "29") (pinfunction "29_29") (pintype "passive"))
    )
    (net (code "101") (name "SDRAM_ADDR_O[1]") (class "Default")
      (node (ref "JP3") (pin "28") (pinfunction "28_28") (pintype "passive"))
    )
    (net (code "102") (name "SDRAM_ADDR_O[2]") (class "Default")
      (node (ref "JP3") (pin "26") (pinfunction "26_26") (pintype "passive"))
    )
    (net (code "103") (name "SDRAM_ADDR_O[3]") (class "Default")
      (node (ref "JP3") (pin "24") (pinfunction "24_24") (pintype "passive"))
    )
    (net (code "104") (name "SDRAM_ADDR_O[4]") (class "Default")
      (node (ref "JP3") (pin "23") (pinfunction "23_23") (pintype "passive"))
    )
    (net (code "105") (name "SDRAM_ADDR_O[5]") (class "Default")
      (node (ref "JP3") (pin "22") (pinfunction "22_22") (pintype "passive"))
    )
    (net (code "106") (name "SDRAM_ADDR_O[6]") (class "Default")
      (node (ref "JP3") (pin "21") (pinfunction "21_21") (pintype "passive"))
    )
    (net (code "107") (name "SDRAM_ADDR_O[7]") (class "Default")
      (node (ref "JP3") (pin "20") (pinfunction "20_20") (pintype "passive"))
    )
    (net (code "108") (name "SDRAM_ADDR_O[8]") (class "Default")
      (node (ref "JP3") (pin "19") (pinfunction "19_19") (pintype "passive"))
    )
    (net (code "109") (name "SDRAM_ADDR_O[9]") (class "Default")
      (node (ref "JP3") (pin "18") (pinfunction "18_18") (pintype "passive"))
    )
    (net (code "110") (name "SDRAM_ADDR_O[10]") (class "Default")
      (node (ref "JP3") (pin "17") (pinfunction "17_17") (pintype "passive"))
    )
    (net (code "111") (name "SDRAM_ADDR_O[11]") (class "Default")
      (node (ref "JP3") (pin "16") (pinfunction "16_16") (pintype "passive"))
    )
    (net (code "112") (name "SDRAM_ADDR_O[12]") (class "Default")
      (node (ref "JP3") (pin "14") (pinfunction "14_14") (pintype "passive"))
    )
    (net (code "113") (name "SDRAM_BA_O[0]") (class "Default")
      (node (ref "JP3") (pin "31") (pinfunction "31_31") (pintype "passive"))
    )
    (net (code "114") (name "SDRAM_BA_O[1]") (class "Default")
      (node (ref "JP3") (pin "30") (pinfunction "30_30") (pintype "passive"))
    )
    (net (code "115") (name "SDRAM_CAS_O") (class "Default")
      (node (ref "JP3") (pin "7") (pinfunction "7_7") (pintype "passive"))
    )
    (net (code "116") (name "SDRAM_CKE_O") (class "Default")
      (node (ref "JP3") (pin "4") (pinfunction "4_4") (pintype "passive"))
    )
    (net (code "117") (name "SDRAM_CLK_O") (class "Default")
      (node (ref "JP3") (pin "2") (pinfunction "2_2") (pintype "passive"))
    )
    (net (code "118") (name "SDRAM_CS_O") (class "Default")
      (node (ref "JP3") (pin "5") (pinfunction "5_5") (pintype "passive"))
    )
    (net (code "119") (name "SDRAM_DATA_I[0]") (class "Default")
      (node (ref "JP4") (pin "38") (pinfunction "38_38") (pintype "passive"))
    )
    (net (code "120") (name "SDRAM_DATA_I[1]") (class "Default")
      (node (ref "JP4") (pin "36") (pinfunction "36_36") (pintype "passive"))
    )
    (net (code "121") (name "SDRAM_DATA_I[2]") (class "Default")
      (node (ref "JP4") (pin "35") (pinfunction "35_35") (pintype "passive"))
    )
    (net (code "122") (name "SDRAM_DATA_I[3]") (class "Default")
      (node (ref "JP4") (pin "34") (pinfunction "34_34") (pintype "passive"))
    )
    (net (code "123") (name "SDRAM_DATA_I[4]") (class "Default")
      (node (ref "JP4") (pin "33") (pinfunction "33_33") (pintype "passive"))
    )
    (net (code "124") (name "SDRAM_DATA_I[5]") (class "Default")
      (node (ref "JP4") (pin "32") (pinfunction "32_32") (pintype "passive"))
    )
    (net (code "125") (name "SDRAM_DATA_I[6]") (class "Default")
      (node (ref "JP4") (pin "31") (pinfunction "31_31") (pintype "passive"))
    )
    (net (code "126") (name "SDRAM_DATA_I[7]") (class "Default")
      (node (ref "JP4") (pin "30") (pinfunction "30_30") (pintype "passive"))
    )
    (net (code "127") (name "SDRAM_DATA_I[8]") (class "Default")
      (node (ref "JP4") (pin "29") (pinfunction "29_29") (pintype "passive"))
    )
    (net (code "128") (name "SDRAM_DATA_I[9]") (class "Default")
      (node (ref "JP4") (pin "28") (pinfunction "28_28") (pintype "passive"))
    )
    (net (code "129") (name "SDRAM_DATA_I[10]") (class "Default")
      (node (ref "JP4") (pin "26") (pinfunction "26_26") (pintype "passive"))
    )
    (net (code "130") (name "SDRAM_DATA_I[11]") (class "Default")
      (node (ref "JP4") (pin "24") (pinfunction "24_24") (pintype "passive"))
    )
    (net (code "131") (name "SDRAM_DATA_I[12]") (class "Default")
      (node (ref "JP4") (pin "23") (pinfunction "23_23") (pintype "passive"))
    )
    (net (code "132") (name "SDRAM_DATA_I[13]") (class "Default")
      (node (ref "JP4") (pin "22") (pinfunction "22_22") (pintype "passive"))
    )
    (net (code "133") (name "SDRAM_DATA_I[14]") (class "Default")
      (node (ref "JP4") (pin "21") (pinfunction "21_21") (pintype "passive"))
    )
    (net (code "134") (name "SDRAM_DATA_I[15]") (class "Default")
      (node (ref "JP4") (pin "20") (pinfunction "20_20") (pintype "passive"))
    )
    (net (code "135") (name "SDRAM_DATA_O[0]") (class "Default")
      (node (ref "JP4") (pin "11") (pinfunction "11_11") (pintype "passive"))
    )
    (net (code "136") (name "SDRAM_DATA_O[1]") (class "Default")
      (node (ref "JP4") (pin "10") (pinfunction "10_10") (pintype "passive"))
    )
    (net (code "137") (name "SDRAM_DATA_O[2]") (class "Default")
      (node (ref "JP4") (pin "9") (pinfunction "9_9") (pintype "passive"))
    )
    (net (code "138") (name "SDRAM_DATA_O[3]") (class "Default")
      (node (ref "JP4") (pin "8") (pinfunction "8_8") (pintype "passive"))
    )
    (net (code "139") (name "SDRAM_DATA_O[4]") (class "Default")
      (node (ref "JP4") (pin "7") (pinfunction "7_7") (pintype "passive"))
    )
    (net (code "140") (name "SDRAM_DATA_O[5]") (class "Default")
      (node (ref "JP4") (pin "6") (pinfunction "6_6") (pintype "passive"))
    )
    (net (code "141") (name "SDRAM_DATA_O[6]") (class "Default")
      (node (ref "JP4") (pin "5") (pinfunction "5_5") (pintype "passive"))
    )
    (net (code "142") (name "SDRAM_DATA_O[7]") (class "Default")
      (node (ref "JP4") (pin "4") (pinfunction "4_4") (pintype "passive"))
    )
    (net (code "143") (name "SDRAM_DATA_O[8]") (class "Default")
      (node (ref "JP4") (pin "2") (pinfunction "2_2") (pintype "passive"))
    )
    (net (code "144") (name "SDRAM_DATA_O[9]") (class "Default")
      (node (ref "JP3") (pin "40") (pinfunction "40_40") (pintype "passive"))
    )
    (net (code "145") (name "SDRAM_DATA_O[10]") (class "Default")
      (node (ref "JP3") (pin "38") (pinfunction "38_38") (pintype "passive"))
    )
    (net (code "146") (name "SDRAM_DATA_O[11]") (class "Default")
      (node (ref "JP3") (pin "36") (pinfunction "36_36") (pintype "passive"))
    )
    (net (code "147") (name "SDRAM_DATA_O[12]") (class "Default")
      (node (ref "JP3") (pin "35") (pinfunction "35_35") (pintype "passive"))
    )
    (net (code "148") (name "SDRAM_DATA_O[13]") (class "Default")
      (node (ref "JP3") (pin "34") (pinfunction "34_34") (pintype "passive"))
    )
    (net (code "149") (name "SDRAM_DATA_O[14]") (class "Default")
      (node (ref "JP3") (pin "33") (pinfunction "33_33") (pintype "passive"))
    )
    (net (code "150") (name "SDRAM_DATA_O[15]") (class "Default")
      (node (ref "JP3") (pin "32") (pinfunction "32_32") (pintype "passive"))
    )
    (net (code "151") (name "SDRAM_DQM_O[0]") (class "Default")
      (node (ref "JP3") (pin "12") (pinfunction "12_12") (pintype "passive"))
    )
    (net (code "152") (name "SDRAM_DQM_O[1]") (class "Default")
      (node (ref "JP3") (pin "11") (pinfunction "11_11") (pintype "passive"))
    )
    (net (code "153") (name "SDRAM_DQM_O[2]") (class "Default")
      (node (ref "JP3") (pin "10") (pinfunction "10_10") (pintype "passive"))
    )
    (net (code "154") (name "SDRAM_DQM_O[3]") (class "Default")
      (node (ref "JP3") (pin "9") (pinfunction "9_9") (pintype "passive"))
    )
    (net (code "155") (name "SDRAM_DRIVE_O") (class "Default")
      (node (ref "JP4") (pin "40") (pinfunction "40_40") (pintype "passive"))
    )
    (net (code "156") (name "SDRAM_RAS_O") (class "Default")
      (node (ref "JP3") (pin "6") (pinfunction "6_6") (pintype "passive"))
    )
    (net (code "157") (name "SDRAM_WE_O") (class "Default")
      (node (ref "JP3") (pin "8") (pinfunction "8_8") (pintype "passive"))
    )
    (net (code "158") (name "SD_QSPI_CS") (class "Default")
      (node (ref "JP1") (pin "23") (pinfunction "23_23") (pintype "passive"))
      (node (ref "SD") (pin "7") (pinfunction "7_7") (pintype "passive"))
    )
    (net (code "159") (name "SD_QSPI_MISO") (class "Default")
      (node (ref "JP1") (pin "26") (pinfunction "26_26") (pintype "passive"))
      (node (ref "SD") (pin "3") (pinfunction "3_3") (pintype "passive"))
    )
    (net (code "160") (name "SD_QSPI_MOSI") (class "Default")
      (node (ref "JP1") (pin "28") (pinfunction "28_28") (pintype "passive"))
      (node (ref "SD") (pin "1") (pinfunction "1_1") (pintype "passive"))
    )
    (net (code "161") (name "SD_QSPI_SCK") (class "Default")
      (node (ref "JP1") (pin "24") (pinfunction "24_24") (pintype "passive"))
      (node (ref "SD") (pin "5") (pinfunction "5_5") (pintype "passive"))
    )
    (net (code "162") (name "SYS_CLK") (class "Default")
      (node (ref "J4") (pin "5") (pinfunction "5_5") (pintype "bidirectional"))
      (node (ref "JP4") (pin "14") (pinfunction "14_14") (pintype "passive"))
      (node (ref "SYS_CLK") (pin "2") (pinfunction "2_2") (pintype "passive"))
    )
    (net (code "163") (name "TCK") (class "Default")
      (node (ref "IC1") (pin "14") (pinfunction "B6_14") (pintype "bidirectional"))
      (node (ref "JTAG_20_PIN") (pin "9") (pinfunction "9_9") (pintype "passive"))
    )
    (net (code "164") (name "TDI") (class "Default")
      (node (ref "IC1") (pin "12") (pinfunction "B8_12") (pintype "bidirectional"))
      (node (ref "JTAG_20_PIN") (pin "5") (pinfunction "5_5") (pintype "passive"))
    )
    (net (code "165") (name "TDO") (class "Default")
      (node (ref "IC1") (pin "13") (pinfunction "B7_13") (pintype "bidirectional"))
      (node (ref "JTAG_20_PIN") (pin "13") (pinfunction "13_13") (pintype "passive"))
    )
    (net (code "166") (name "TMS") (class "Default")
      (node (ref "IC1") (pin "15") (pinfunction "B5_15") (pintype "bidirectional"))
      (node (ref "JTAG_20_PIN") (pin "7") (pinfunction "7_7") (pintype "passive"))
    )
    (net (code "167") (name "TX") (class "Default")
      (node (ref "IC2") (pin "17") (pinfunction "B3_17") (pintype "bidirectional"))
      (node (ref "USB-UART_1") (pin "4") (pinfunction "4_4") (pintype "passive"))
    )
    (net (code "168") (name "UART_RXD") (class "Default")
      (node (ref "JP1") (pin "30") (pinfunction "30_30") (pintype "passive"))
      (node (ref "UART") (pin "1") (pinfunction "1_1") (pintype "passive"))
    )
    (net (code "169") (name "UART_TXD") (class "Default")
      (node (ref "JP1") (pin "29") (pinfunction "29_29") (pintype "passive"))
      (node (ref "UART") (pin "3") (pinfunction "3_3") (pintype "passive"))
    )
    (net (code "170") (name "VDD") (class "Default")
      (node (ref "C12") (pin "1") (pinfunction "1_1") (pintype "passive"))
      (node (ref "C13") (pin "1") (pinfunction "1_1") (pintype "passive"))
      (node (ref "JP1") (pin "13") (pinfunction "13_13") (pintype "passive"))
      (node (ref "JP1") (pin "39") (pinfunction "39_39") (pintype "passive"))
      (node (ref "JP2") (pin "13") (pinfunction "13_13") (pintype "passive"))
      (node (ref "JP2") (pin "39") (pinfunction "39_39") (pintype "passive"))
      (node (ref "JP3") (pin "15") (pinfunction "15_15") (pintype "passive"))
      (node (ref "JP3") (pin "39") (pinfunction "39_39") (pintype "passive"))
      (node (ref "JP4") (pin "13") (pinfunction "13_13") (pintype "passive"))
      (node (ref "JP4") (pin "39") (pinfunction "39_39") (pintype "passive"))
      (node (ref "POWER") (pin "2") (pinfunction "2_2") (pintype "passive"))
      (node (ref "POWER_LED") (pin "1") (pinfunction "1_1") (pintype "passive"))
    )
    (net (code "171") (name "VDDO") (class "Default")
      (node (ref "C1") (pin "1") (pinfunction "1_1") (pintype "passive"))
      (node (ref "C11") (pin "1") (pinfunction "1_1") (pintype "passive"))
      (node (ref "C14") (pin "1") (pinfunction "1_1") (pintype "passive"))
      (node (ref "C3") (pin "1") (pinfunction "1_1") (pintype "passive"))
      (node (ref "IC1") (pin "10") (pinfunction "OE_10") (pintype "bidirectional"))
      (node (ref "IC1") (pin "2") (pinfunction "VCCA_2") (pintype "bidirectional"))
      (node (ref "IC2") (pin "10") (pinfunction "OE_10") (pintype "bidirectional"))
      (node (ref "IC2") (pin "2") (pinfunction "VCCA_2") (pintype "bidirectional"))
      (node (ref "JP1") (pin "1") (pinfunction "1_1") (pintype "passive"))
      (node (ref "JP1") (pin "27") (pinfunction "27_27") (pintype "passive"))
      (node (ref "JP2") (pin "1") (pinfunction "1_1") (pintype "passive"))
      (node (ref "JP2") (pin "25") (pinfunction "25_25") (pintype "passive"))
      (node (ref "JP3") (pin "1") (pinfunction "1_1") (pintype "passive"))
      (node (ref "JP3") (pin "25") (pinfunction "25_25") (pintype "passive"))
      (node (ref "JP4") (pin "1") (pinfunction "1_1") (pintype "passive"))
      (node (ref "JP4") (pin "27") (pinfunction "27_27") (pintype "passive"))
      (node (ref "POWER") (pin "4") (pinfunction "4_4") (pintype "passive"))
      (node (ref "POWER_LED") (pin "3") (pinfunction "3_3") (pintype "passive"))
    )
    (net (code "172") (name "VDDO_LED") (class "Default")
      (node (ref "POWER_LED") (pin "4") (pinfunction "4_4") (pintype "passive"))
      (node (ref "Q6") (pin "1") (pinfunction "G_1") (pintype "bidirectional"))
      (node (ref "R12") (pin "2") (pinfunction "2_2") (pintype "passive"))
    )
    (net (code "173") (name "VDD_1.8_1") (class "Default")
      (node (ref "C10") (pin "1") (pinfunction "1_1") (pintype "passive"))
      (node (ref "IC5") (pin "2") (pinfunction "VOUT_1_2") (pintype "bidirectional"))
      (node (ref "IC5") (pin "4") (pinfunction "VOUT_2_4") (pintype "bidirectional"))
      (node (ref "POWER") (pin "1") (pinfunction "1_1") (pintype "passive"))
    )
    (net (code "174") (name "VDD_1.8_2") (class "Default")
      (node (ref "C6") (pin "1") (pinfunction "1_1") (pintype "passive"))
      (node (ref "IC3") (pin "2") (pinfunction "VOUT_1_2") (pintype "bidirectional"))
      (node (ref "IC3") (pin "4") (pinfunction "VOUT_2_4") (pintype "bidirectional"))
      (node (ref "POWER") (pin "3") (pinfunction "3_3") (pintype "passive"))
    )
    (net (code "175") (name "VDD_3V3") (class "Default")
      (node (ref "3.3V_GPIO") (pin "1") (pinfunction "1_1") (pintype "passive"))
      (node (ref "C2") (pin "1") (pinfunction "1_1") (pintype "passive"))
      (node (ref "C4") (pin "1") (pinfunction "1_1") (pintype "passive"))
      (node (ref "C5") (pin "1") (pinfunction "1_1") (pintype "passive"))
      (node (ref "C9") (pin "1") (pinfunction "1_1") (pintype "passive"))
      (node (ref "FLASH") (pin "1") (pinfunction "1_1") (pintype "passive"))
      (node (ref "FLASH") (pin "2") (pinfunction "2_2") (pintype "passive"))
      (node (ref "IC1") (pin "19") (pinfunction "VCCB_19") (pintype "bidirectional"))
      (node (ref "IC2") (pin "19") (pinfunction "VCCB_19") (pintype "bidirectional"))
      (node (ref "IC3") (pin "3") (pinfunction "VIN_3") (pintype "bidirectional"))
      (node (ref "IC5") (pin "3") (pinfunction "VIN_3") (pintype "bidirectional"))
      (node (ref "JTAG_20_PIN") (pin "1") (pinfunction "1_1") (pintype "passive"))
      (node (ref "JTAG_20_PIN") (pin "2") (pinfunction "2_2") (pintype "passive"))
      (node (ref "Q5") (pin "1") (pinfunction "G_1") (pintype "bidirectional"))
      (node (ref "R11") (pin "2") (pinfunction "2_2") (pintype "passive"))
      (node (ref "R13") (pin "2") (pinfunction "2_2") (pintype "passive"))
      (node (ref "R15") (pin "2") (pinfunction "2_2") (pintype "passive"))
      (node (ref "R16") (pin "2") (pinfunction "2_2") (pintype "passive"))
      (node (ref "R17") (pin "2") (pinfunction "2_2") (pintype "passive"))
      (node (ref "SD_CARD") (pin "1") (pinfunction "1_1") (pintype "passive"))
      (node (ref "SD_CARD") (pin "2") (pinfunction "2_2") (pintype "passive"))
      (node (ref "USB-UART_1") (pin "3") (pinfunction "3_3") (pintype "passive"))
    )
    (net (code "176") (name "VDD_3V3_GPIO") (class "Default")
      (node (ref "3.3V_GPIO") (pin "2") (pinfunction "2_2") (pintype "passive"))
      (node (ref "GPIO_1") (pin "29") (pinfunction "29_29") (pintype "passive"))
      (node (ref "GPIO_2") (pin "29") (pinfunction "29_29") (pintype "passive"))
    )
    (net (code "177") (name "VDD_5V_USB") (class "Default")
      (node (ref "USB-UART_2") (pin "2") (pinfunction "2_2") (pintype "passive"))
    )
    (net (code "178") (name "VDD_LED") (class "Default")
      (node (ref "POWER_LED") (pin "2") (pinfunction "2_2") (pintype "passive"))
      (node (ref "Q8") (pin "1") (pinfunction "G_1") (pintype "bidirectional"))
      (node (ref "R10") (pin "2") (pinfunction "2_2") (pintype "passive"))
    )
    (net (code "179") (name "unconnected-(FLASH-Pad5)") (class "Default")
      (node (ref "FLASH") (pin "5") (pinfunction "5_5") (pintype "passive"))
    )
    (net (code "180") (name "unconnected-(FLASH-Pad7)") (class "Default")
      (node (ref "FLASH") (pin "7") (pinfunction "7_7") (pintype "passive"))
    )
    (net (code "181") (name "unconnected-(FLASH-Pad9)") (class "Default")
      (node (ref "FLASH") (pin "9") (pinfunction "9_9") (pintype "passive"))
    )
    (net (code "182") (name "unconnected-(FLASH-Pad11)") (class "Default")
      (node (ref "FLASH") (pin "11") (pinfunction "11_11") (pintype "passive"))
    )
    (net (code "183") (name "unconnected-(GPIO_1-Pad1)") (class "Default")
      (node (ref "GPIO_1") (pin "1") (pinfunction "1_1") (pintype "passive"))
    )
    (net (code "184") (name "unconnected-(GPIO_1-Pad3)") (class "Default")
      (node (ref "GPIO_1") (pin "3") (pinfunction "3_3") (pintype "passive"))
    )
    (net (code "185") (name "unconnected-(GPIO_1-Pad11)") (class "Default")
      (node (ref "GPIO_1") (pin "11") (pinfunction "11_11") (pintype "passive"))
    )
    (net (code "186") (name "unconnected-(GPIO_2-Pad1)") (class "Default")
      (node (ref "GPIO_2") (pin "1") (pinfunction "1_1") (pintype "passive"))
    )
    (net (code "187") (name "unconnected-(GPIO_2-Pad3)") (class "Default")
      (node (ref "GPIO_2") (pin "3") (pinfunction "3_3") (pintype "passive"))
    )
    (net (code "188") (name "unconnected-(GPIO_2-Pad9)") (class "Default")
      (node (ref "GPIO_2") (pin "9") (pinfunction "9_9") (pintype "passive"))
    )
    (net (code "189") (name "unconnected-(GPIO_2-Pad10)") (class "Default")
      (node (ref "GPIO_2") (pin "10") (pinfunction "10_10") (pintype "passive"))
    )
    (net (code "190") (name "unconnected-(GPIO_2-Pad11)") (class "Default")
      (node (ref "GPIO_2") (pin "11") (pinfunction "11_11") (pintype "passive"))
    )
    (net (code "191") (name "unconnected-(GPIO_2-Pad13)") (class "Default")
      (node (ref "GPIO_2") (pin "13") (pinfunction "13_13") (pintype "passive"))
    )
    (net (code "192") (name "unconnected-(GPIO_2-Pad14)") (class "Default")
      (node (ref "GPIO_2") (pin "14") (pinfunction "14_14") (pintype "passive"))
    )
    (net (code "193") (name "unconnected-(GPIO_2-Pad15)") (class "Default")
      (node (ref "GPIO_2") (pin "15") (pinfunction "15_15") (pintype "passive"))
    )
    (net (code "194") (name "unconnected-(GPIO_2-Pad16)") (class "Default")
      (node (ref "GPIO_2") (pin "16") (pinfunction "16_16") (pintype "passive"))
    )
    (net (code "195") (name "unconnected-(GPIO_2-Pad17)") (class "Default")
      (node (ref "GPIO_2") (pin "17") (pinfunction "17_17") (pintype "passive"))
    )
    (net (code "196") (name "unconnected-(GPIO_2-Pad18)") (class "Default")
      (node (ref "GPIO_2") (pin "18") (pinfunction "18_18") (pintype "passive"))
    )
    (net (code "197") (name "unconnected-(GPIO_2-Pad19)") (class "Default")
      (node (ref "GPIO_2") (pin "19") (pinfunction "19_19") (pintype "passive"))
    )
    (net (code "198") (name "unconnected-(GPIO_2-Pad20)") (class "Default")
      (node (ref "GPIO_2") (pin "20") (pinfunction "20_20") (pintype "passive"))
    )
    (net (code "199") (name "unconnected-(GPIO_2-Pad21)") (class "Default")
      (node (ref "GPIO_2") (pin "21") (pinfunction "21_21") (pintype "passive"))
    )
    (net (code "200") (name "unconnected-(GPIO_2-Pad22)") (class "Default")
      (node (ref "GPIO_2") (pin "22") (pinfunction "22_22") (pintype "passive"))
    )
    (net (code "201") (name "unconnected-(GPIO_2-Pad23)") (class "Default")
      (node (ref "GPIO_2") (pin "23") (pinfunction "23_23") (pintype "passive"))
    )
    (net (code "202") (name "unconnected-(GPIO_2-Pad24)") (class "Default")
      (node (ref "GPIO_2") (pin "24") (pinfunction "24_24") (pintype "passive"))
    )
    (net (code "203") (name "unconnected-(GPIO_2-Pad25)") (class "Default")
      (node (ref "GPIO_2") (pin "25") (pinfunction "25_25") (pintype "passive"))
    )
    (net (code "204") (name "unconnected-(GPIO_2-Pad26)") (class "Default")
      (node (ref "GPIO_2") (pin "26") (pinfunction "26_26") (pintype "passive"))
    )
    (net (code "205") (name "unconnected-(GPIO_2-Pad27)") (class "Default")
      (node (ref "GPIO_2") (pin "27") (pinfunction "27_27") (pintype "passive"))
    )
    (net (code "206") (name "unconnected-(GPIO_2-Pad28)") (class "Default")
      (node (ref "GPIO_2") (pin "28") (pinfunction "28_28") (pintype "passive"))
    )
    (net (code "207") (name "unconnected-(GPIO_2-Pad31)") (class "Default")
      (node (ref "GPIO_2") (pin "31") (pinfunction "31_31") (pintype "passive"))
    )
    (net (code "208") (name "unconnected-(GPIO_2-Pad32)") (class "Default")
      (node (ref "GPIO_2") (pin "32") (pinfunction "32_32") (pintype "passive"))
    )
    (net (code "209") (name "unconnected-(GPIO_2-Pad33)") (class "Default")
      (node (ref "GPIO_2") (pin "33") (pinfunction "33_33") (pintype "passive"))
    )
    (net (code "210") (name "unconnected-(GPIO_2-Pad34)") (class "Default")
      (node (ref "GPIO_2") (pin "34") (pinfunction "34_34") (pintype "passive"))
    )
    (net (code "211") (name "unconnected-(IC2-A1-Pad1)") (class "Default")
      (node (ref "IC2") (pin "1") (pinfunction "A1_1") (pintype "bidirectional"))
    )
    (net (code "212") (name "unconnected-(IC2-A8-Pad9)") (class "Default")
      (node (ref "IC2") (pin "9") (pinfunction "A8_9") (pintype "bidirectional"))
    )
    (net (code "213") (name "unconnected-(IC2-B1-Pad20)") (class "Default")
      (node (ref "IC2") (pin "20") (pinfunction "B1_20") (pintype "bidirectional"))
    )
    (net (code "214") (name "unconnected-(IC2-B8-Pad12)") (class "Default")
      (node (ref "IC2") (pin "12") (pinfunction "B8_12") (pintype "bidirectional"))
    )
    (net (code "215") (name "unconnected-(JTAG_20_PIN-Pad3)") (class "Default")
      (node (ref "JTAG_20_PIN") (pin "3") (pinfunction "3_3") (pintype "passive"))
    )
    (net (code "216") (name "unconnected-(JTAG_20_PIN-Pad11)") (class "Default")
      (node (ref "JTAG_20_PIN") (pin "11") (pinfunction "11_11") (pintype "passive"))
    )
    (net (code "217") (name "unconnected-(JTAG_20_PIN-Pad15)") (class "Default")
      (node (ref "JTAG_20_PIN") (pin "15") (pinfunction "15_15") (pintype "passive"))
    )
    (net (code "218") (name "unconnected-(JTAG_20_PIN-Pad17)") (class "Default")
      (node (ref "JTAG_20_PIN") (pin "17") (pinfunction "17_17") (pintype "passive"))
    )
    (net (code "219") (name "unconnected-(JTAG_20_PIN-Pad19)") (class "Default")
      (node (ref "JTAG_20_PIN") (pin "19") (pinfunction "19_19") (pintype "passive"))
    )
    (net (code "220") (name "unconnected-(SD_CARD-Pad5)") (class "Default")
      (node (ref "SD_CARD") (pin "5") (pinfunction "5_5") (pintype "passive"))
    )
    (net (code "221") (name "unconnected-(SD_CARD-Pad7)") (class "Default")
      (node (ref "SD_CARD") (pin "7") (pinfunction "7_7") (pintype "passive"))
    )
    (net (code "222") (name "unconnected-(SD_CARD-Pad9)") (class "Default")
      (node (ref "SD_CARD") (pin "9") (pinfunction "9_9") (pintype "passive"))
    )
    (net (code "223") (name "unconnected-(SD_CARD-Pad11)") (class "Default")
      (node (ref "SD_CARD") (pin "11") (pinfunction "11_11") (pintype "passive"))
    )
    (net (code "224") (name "unconnected-(USB-UART_2-Pad1)") (class "Default")
      (node (ref "USB-UART_2") (pin "1") (pinfunction "1_1") (pintype "passive"))
    )
    (net (code "225") (name "unconnected-(USB-UART_2-Pad3)") (class "Default")
      (node (ref "USB-UART_2") (pin "3") (pinfunction "3_3") (pintype "passive"))
    )
    (net (code "226") (name "unconnected-(USB-UART_2-Pad4)") (class "Default")
      (node (ref "USB-UART_2") (pin "4") (pinfunction "4_4") (pintype "passive"))
    )
  )
)
